# EasyEDAPro_River_Gauge_Rev_2_2026-01-11.net
KiCad netlist of a schematic drawn in EasyEDA Pro
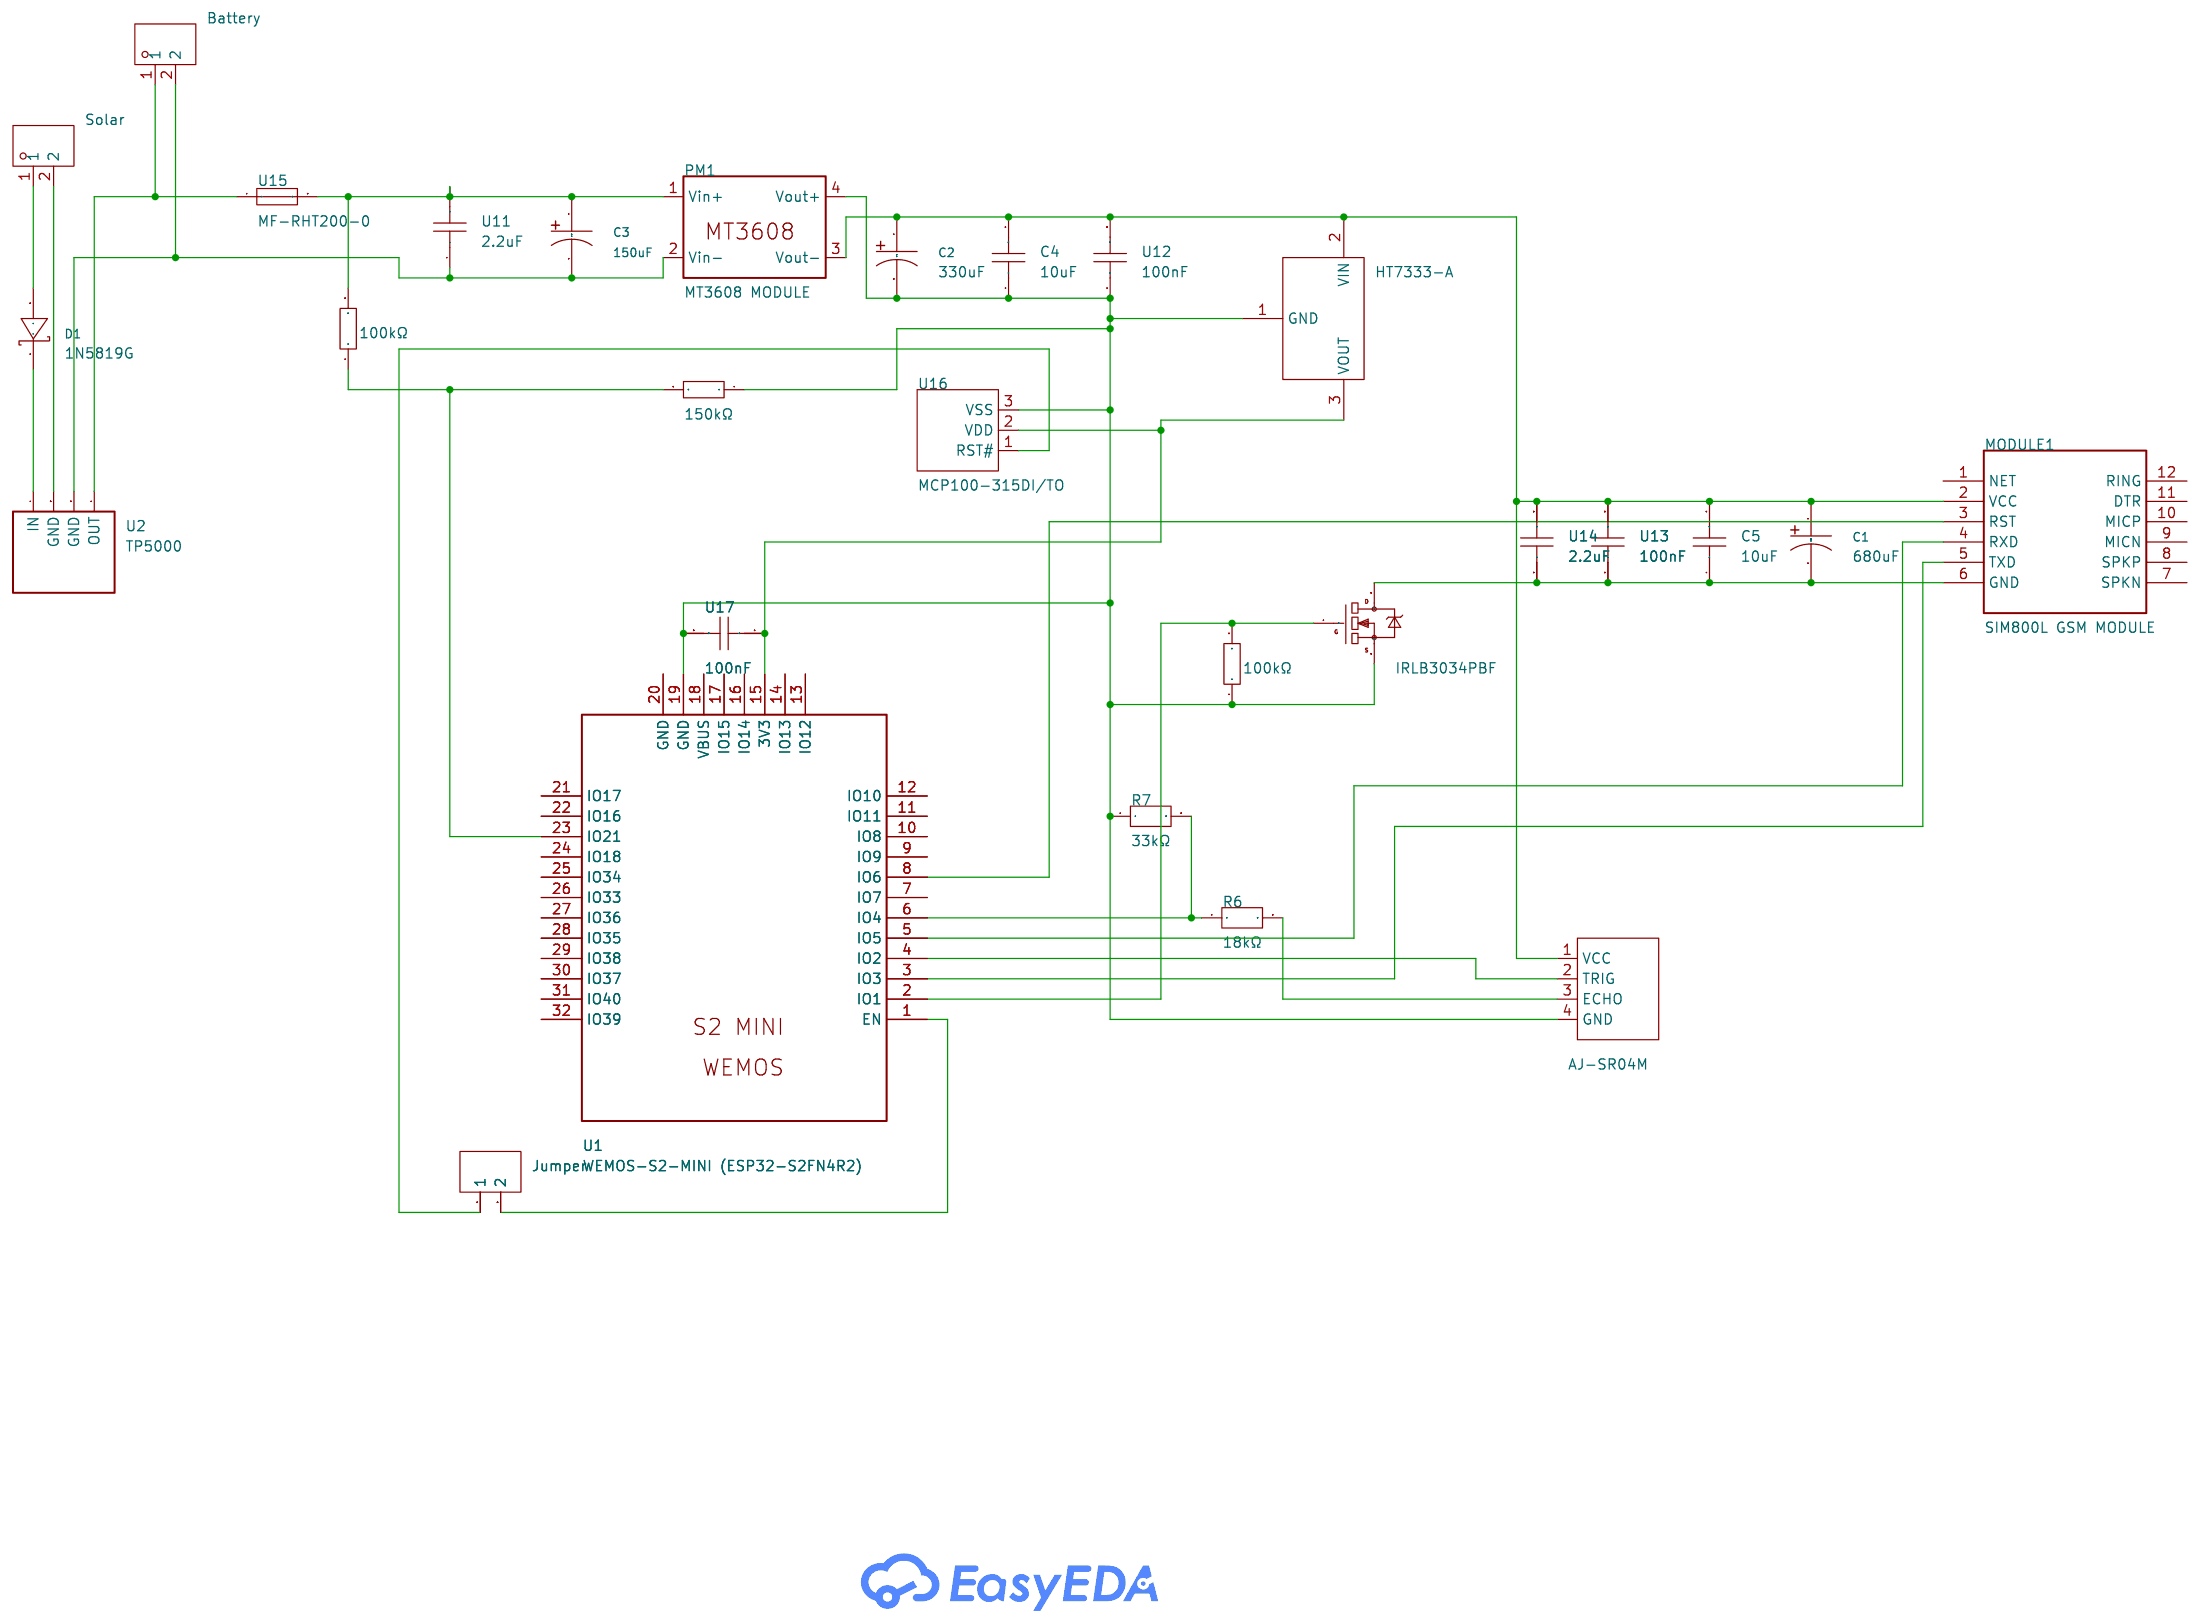
[diagram p0: schematic sheet]

(export (version "E")
  (design (tool "Eeschema 10.0.6"))
  (components
    (comp (ref "C1")
      (value "680uF")
      (footprint "easyedapro:CAP-TH_BD8.0-P3.50-D0.6-FD_1")
      (fields (field (name "Manufacturer Part") "EEUFR1A681") (field (name "Manufacturer") "PANASONIC(松下)"))
      (libsource (lib "easyedapro") (part "EEUFR1A681"))
    )
    (comp (ref "C2")
      (value "330uF")
      (footprint "easyedapro:CAP-TH_BD6.3-P2.50-D1.0-FD")
      (fields (field (name "Manufacturer Part") "EEUFS1A331") (field (name "Manufacturer") "PANASONIC(松下)"))
      (libsource (lib "easyedapro") (part "EEUFS1A331"))
    )
    (comp (ref "C3")
      (value "150uF")
      (footprint "easyedapro:CAP-TH_BD6.3-P2.50-D1.0-FD")
      (fields (field (name "Manufacturer Part") "EEUFS1A331") (field (name "Manufacturer") "PANASONIC(松下)"))
      (libsource (lib "easyedapro") (part "EEUFS1A331"))
    )
    (comp (ref "C4")
      (value "10uF")
      (footprint "easyedapro:CAP-TH_L4.5-W3.0-P2.50-D0.5")
      (fields (field (name "Manufacturer Part") "FG14X7R1A106KRT06") (field (name "Manufacturer") "TDK"))
      (libsource (lib "easyedapro") (part "FG14X7R1A106KRT06"))
    )
    (comp (ref "C5")
      (value "10uF")
      (footprint "easyedapro:CAP-TH_L4.5-W3.0-P2.50-D0.5")
      (fields (field (name "Manufacturer Part") "FG14X7R1A106KRT06") (field (name "Manufacturer") "TDK"))
      (libsource (lib "easyedapro") (part "FG14X7R1A106KRT06"))
    )
    (comp (ref "D1")
      (value "1N5819G")
      (footprint "easyedapro:DO-41_BD2.4-L4.7-P8.70-D0.9-RD")
      (fields (field (name "Manufacturer") "onsemi(安森美)"))
      (libsource (lib "easyedapro") (part "1N5819G"))
    )
    (comp (ref "H1")
      (value "Jumper")
      (footprint "easyedapro:HDR-TH_2P-P2.54-V-F")
      (libsource (lib "easyedapro") (part "Header-Female-2.54_1x2"))
    )
    (comp (ref "MODULE1")
      (value "SIM800L GSM MODULE")
      (footprint "easyedapro:SIM800L GSM MODULE")
      (libsource (lib "easyedapro") (part "SIM800L GSM MODULE"))
    )
    (comp (ref "PM1")
      (value "MT3608 MODULE")
      (footprint "easyedapro:MT3608")
      (libsource (lib "easyedapro") (part "MT3608 MODULE"))
    )
    (comp (ref "Q2")
      (value "IRLB3034PBF")
      (footprint "easyedapro:TO-220-3_L10.0-W4.5-P2.54-L")
      (fields (field (name "Manufacturer") "Infineon(英飞凌)"))
      (libsource (lib "easyedapro") (part "IRLB3034PBF"))
    )
    (comp (ref "R2")
      (value "100kΩ")
      (footprint "easyedapro:RES-TH_BD4.5-L11.0-P15.00-D0.7")
      (fields (field (name "Manufacturer Part") "MO2WS-100K±5%-TT63") (field (name "Manufacturer") "VO(翔胜)"))
      (libsource (lib "easyedapro") (part "MO2WS-100K±5%-TT63"))
    )
    (comp (ref "R3")
      (value "100kΩ")
      (footprint "easyedapro:RES-TH_BD4.5-L11.0-P15.00-D0.7")
      (fields (field (name "Manufacturer Part") "MO2WS-100K±5%-TT63") (field (name "Manufacturer") "VO(翔胜)"))
      (libsource (lib "easyedapro") (part "MO2WS-100K±5%-TT63"))
    )
    (comp (ref "R4")
      (value "150kΩ")
      (footprint "easyedapro:RES-TH_BD4.5-L11.0-P15.00-D0.7")
      (fields (field (name "Manufacturer Part") "MO2WS-100K±5%-TT63") (field (name "Manufacturer") "VO(翔胜)"))
      (libsource (lib "easyedapro") (part "MO2WS-100K±5%-TT63"))
    )
    (comp (ref "R6")
      (value "18kΩ")
      (footprint "easyedapro:RES-TH_BD2.4-L6.5-P10.50-D0.5")
      (fields
        (field (name "Manufacturer Part") "RNF14FTC18K0")
        (field (name "Manufacturer") "SEI(Stackpole Electronics Inc.)")
      )
      (libsource (lib "easyedapro") (part "RNF14FTC18K0"))
    )
    (comp (ref "R7")
      (value "33kΩ")
      (footprint "easyedapro:RES-TH_BD2.4-L6.5-P10.50-D0.5")
      (fields
        (field (name "Manufacturer Part") "RNF14FTC18K0")
        (field (name "Manufacturer") "SEI(Stackpole Electronics Inc.)")
      )
      (libsource (lib "easyedapro") (part "RNF14FTC18K0"))
    )
    (comp (ref "U1")
      (value "WEMOS-S2-MINI (ESP32-S2FN4R2)")
      (footprint "easyedapro:WEMOS-S2-MINI")
      (fields (field (name "Manufacturer Part") "Wemos") (field (name "Manufacturer") "WEMOS"))
      (libsource (lib "easyedapro") (part "WEMOS-S2-MINI (ESP32-S2FN4R2)"))
    )
    (comp (ref "U2")
      (value "TP5000")
      (footprint "easyedapro:TP5000")
      (libsource (lib "easyedapro") (part "TP5000"))
    )
    (comp (ref "U7")
      (value "Solar")
      (footprint "easyedapro:CONN-TH_2P-P3.50_KEFA_KF2EDGJVC-3.5-2P")
      (fields (field (name "Manufacturer Part") "KF2EDGJVC-3.5-2P"))
      (libsource (lib "easyedapro") (part "KF2EDGJVC-3.5-2P"))
    )
    (comp (ref "U8")
      (value "Battery")
      (footprint "easyedapro:CONN-TH_2P-P3.50_KEFA_KF2EDGJVC-3.5-2P")
      (fields (field (name "Manufacturer Part") "KF2EDGJVC-3.5-2P"))
      (libsource (lib "easyedapro") (part "KF2EDGJVC-3.5-2P"))
    )
    (comp (ref "U9")
      (value "AJ-SR04M")
      (footprint "easyedapro:TH_HC-SR04V")
      (fields
        (field (name "Manufacturer Part") "HC-SR04")
        (field (name "Manufacturer") "Universal Microelectronics")
      )
      (libsource (lib "easyedapro") (part "HC-SR04"))
    )
    (comp (ref "U10")
      (value "HT7333-A")
      (footprint "easyedapro:TO-92-3_L5.1-W4.1-P1.27-L")
      (fields (field (name "Manufacturer") "HOLTEK(合泰/盛群)"))
      (libsource (lib "easyedapro") (part "HT7333-A_C73726"))
    )
    (comp (ref "U11")
      (value "2.2uF")
      (footprint "easyedapro:CAP-TH_L4.0-W2.5-P2.50-D0.5")
      (fields (field (name "Manufacturer Part") "FG18X7R1A225KRT06") (field (name "Manufacturer") "TDK"))
      (libsource (lib "easyedapro") (part "FG18X7R1A225KRT06"))
    )
    (comp (ref "U12")
      (value "100nF")
      (footprint "easyedapro:CAP-TH_L3.6-W2.3-P2.5-D0.6")
      (description "Capacitance:100nF Tolerance:±10% Tolerance:±10% Voltage Rating:50V Temperature Coefficient:X7R")
      (fields (field (name "Manufacturer Part") "K104K15X7RF53L2") (field (name "Manufacturer") "VISHAY(威世)"))
      (libsource (lib "easyedapro") (part "K104K15X7RF53L2"))
    )
    (comp (ref "U13")
      (value "100nF")
      (footprint "easyedapro:CAP-TH_L3.6-W2.3-P2.5-D0.6")
      (description "Capacitance:100nF Tolerance:±10% Tolerance:±10% Voltage Rating:50V Temperature Coefficient:X7R")
      (fields (field (name "Manufacturer Part") "K104K15X7RF53L2") (field (name "Manufacturer") "VISHAY(威世)"))
      (libsource (lib "easyedapro") (part "K104K15X7RF53L2"))
    )
    (comp (ref "U14")
      (value "2.2uF")
      (footprint "easyedapro:CAP-TH_L4.0-W2.5-P2.50-D0.5")
      (fields (field (name "Manufacturer Part") "FG18X7R1A225KRT06") (field (name "Manufacturer") "TDK"))
      (libsource (lib "easyedapro") (part "FG18X7R1A225KRT06"))
    )
    (comp (ref "U15")
      (value "MF-RHT200-0")
      (footprint "easyedapro:FUSE-TH_L9.4-W3.0-P5.10-D1.0-S2.10")
      (fields (field (name "Manufacturer") "BOURNS"))
      (libsource (lib "easyedapro") (part "MF-RHT200-0"))
    )
    (comp (ref "U16")
      (value "MCP100-315DI/TO")
      (footprint "easyedapro:TO-92-3_L4.8-W3.7-P1.27-L")
      (fields (field (name "Manufacturer") "MICROCHIP(美国微芯)"))
      (libsource (lib "easyedapro") (part "MCP100-315DI/TO"))
    )
    (comp (ref "U17")
      (value "100nF")
      (footprint "easyedapro:CAP-TH_L3.6-W2.3-P2.5-D0.6")
      (description "Capacitance:100nF Tolerance:±10% Tolerance:±10% Voltage Rating:50V Temperature Coefficient:X7R")
      (fields (field (name "Manufacturer Part") "K104K15X7RF53L2") (field (name "Manufacturer") "VISHAY(威世)"))
      (libsource (lib "easyedapro") (part "K104K15X7RF53L2"))
    )
  )
  (nets
    (net (code "1") (name "Net-(D1-A)") (class "Default")
      (node (ref "D1") (pin "2") (pinfunction "A_2") (pintype "input"))
      (node (ref "U7") (pin "1") (pinfunction "1_1") (pintype "unspecified"))
    )
    (net (code "2") (name "Net-(D1-K)") (class "Default")
      (node (ref "D1") (pin "1") (pinfunction "K_1") (pintype "input"))
      (node (ref "U2") (pin "4") (pinfunction "IN_4") (pintype "unspecified"))
    )
    (net (code "3") (name "Net-(MODULE1-GND)") (class "Default")
      (node (ref "C1") (pin "2") (pinfunction "2_2") (pintype "input"))
      (node (ref "C5") (pin "1") (pinfunction "1_1") (pintype "unspecified"))
      (node (ref "MODULE1") (pin "6") (pinfunction "GND_6") (pintype "unspecified"))
      (node (ref "Q2") (pin "2") (pinfunction "D_2") (pintype "unspecified"))
      (node (ref "U13") (pin "1") (pinfunction "1_1") (pintype "unspecified"))
      (node (ref "U14") (pin "1") (pinfunction "1_1") (pintype "unspecified"))
    )
    (net (code "4") (name "Net-(MODULE1-RST)") (class "Default")
      (node (ref "MODULE1") (pin "3") (pinfunction "RST_3") (pintype "unspecified"))
      (node (ref "U1") (pin "8") (pinfunction "IO6_8") (pintype "bidirectional"))
    )
    (net (code "5") (name "Net-(MODULE1-RXD)") (class "Default")
      (node (ref "MODULE1") (pin "4") (pinfunction "RXD_4") (pintype "unspecified"))
      (node (ref "U1") (pin "5") (pinfunction "IO5_5") (pintype "bidirectional"))
    )
    (net (code "6") (name "Net-(MODULE1-TXD)") (class "Default")
      (node (ref "MODULE1") (pin "5") (pinfunction "TXD_5") (pintype "unspecified"))
      (node (ref "U1") (pin "3") (pinfunction "IO3_3") (pintype "bidirectional"))
    )
    (net (code "7") (name "Net-(MODULE1-VCC)") (class "Default")
      (node (ref "C1") (pin "1") (pinfunction "1_1") (pintype "input"))
      (node (ref "C2") (pin "1") (pinfunction "1_1") (pintype "input"))
      (node (ref "C4") (pin "2") (pinfunction "2_2") (pintype "unspecified"))
      (node (ref "C5") (pin "2") (pinfunction "2_2") (pintype "unspecified"))
      (node (ref "MODULE1") (pin "2") (pinfunction "VCC_2") (pintype "unspecified"))
      (node (ref "PM1") (pin "3") (pinfunction "Vout-_3") (pintype "unspecified"))
      (node (ref "U10") (pin "2") (pinfunction "VIN_2") (pintype "unspecified"))
      (node (ref "U12") (pin "2") (pinfunction "2_2") (pintype "unspecified"))
      (node (ref "U13") (pin "2") (pinfunction "2_2") (pintype "unspecified"))
      (node (ref "U14") (pin "2") (pinfunction "2_2") (pintype "unspecified"))
      (node (ref "U9") (pin "1") (pinfunction "VCC_1") (pintype "unspecified"))
    )
    (net (code "8") (name "Net-(PM1-Vin+)") (class "Default")
      (node (ref "C3") (pin "1") (pinfunction "1_1") (pintype "input"))
      (node (ref "PM1") (pin "1") (pinfunction "Vin+_1") (pintype "unspecified"))
      (node (ref "R3") (pin "2") (pinfunction "2_2") (pintype "unspecified"))
      (node (ref "U11") (pin "2") (pinfunction "2_2") (pintype "unspecified"))
      (node (ref "U15") (pin "2") (pinfunction "2_2") (pintype "unspecified"))
    )
    (net (code "9") (name "Net-(PM1-Vin-)") (class "Default")
      (node (ref "C3") (pin "2") (pinfunction "2_2") (pintype "input"))
      (node (ref "PM1") (pin "2") (pinfunction "Vin-_2") (pintype "unspecified"))
      (node (ref "U11") (pin "1") (pinfunction "1_1") (pintype "unspecified"))
      (node (ref "U2") (pin "2") (pinfunction "GND_2") (pintype "unspecified"))
      (node (ref "U8") (pin "2") (pinfunction "2_2") (pintype "unspecified"))
    )
    (net (code "10") (name "Net-(PM1-Vout+)") (class "Default")
      (node (ref "C2") (pin "2") (pinfunction "2_2") (pintype "input"))
      (node (ref "C4") (pin "1") (pinfunction "1_1") (pintype "unspecified"))
      (node (ref "PM1") (pin "4") (pinfunction "Vout+_4") (pintype "unspecified"))
      (node (ref "Q2") (pin "3") (pinfunction "S_3") (pintype "unspecified"))
      (node (ref "R2") (pin "1") (pinfunction "1_1") (pintype "unspecified"))
      (node (ref "R4") (pin "1") (pinfunction "1_1") (pintype "unspecified"))
      (node (ref "R7") (pin "1") (pinfunction "1_1") (pintype "unspecified"))
      (node (ref "U1") (pin "19") (pinfunction "GND_19") (pintype "unspecified"))
      (node (ref "U10") (pin "1") (pinfunction "GND_1") (pintype "unspecified"))
      (node (ref "U12") (pin "1") (pinfunction "1_1") (pintype "unspecified"))
      (node (ref "U16") (pin "3") (pinfunction "VSS_3") (pintype "unspecified"))
      (node (ref "U17") (pin "2") (pinfunction "2_2") (pintype "unspecified"))
      (node (ref "U9") (pin "4") (pinfunction "GND_4") (pintype "unspecified"))
    )
    (net (code "11") (name "Net-(Q2-G)") (class "Default")
      (node (ref "Q2") (pin "1") (pinfunction "G_1") (pintype "unspecified"))
      (node (ref "R2") (pin "2") (pinfunction "2_2") (pintype "unspecified"))
      (node (ref "U1") (pin "2") (pinfunction "IO1_2") (pintype "bidirectional"))
    )
    (net (code "12") (name "Net-(U1-3V3)") (class "Default")
      (node (ref "U1") (pin "15") (pinfunction "3V3_15") (pintype "unspecified"))
      (node (ref "U10") (pin "3") (pinfunction "VOUT_3") (pintype "unspecified"))
      (node (ref "U16") (pin "2") (pinfunction "VDD_2") (pintype "unspecified"))
      (node (ref "U17") (pin "1") (pinfunction "1_1") (pintype "unspecified"))
    )
    (net (code "13") (name "Net-(U1-EN)") (class "Default")
      (node (ref "H1") (pin "2") (pinfunction "2_2") (pintype "input"))
      (node (ref "U1") (pin "1") (pinfunction "EN_1") (pintype "input"))
    )
    (net (code "14") (name "Net-(U1-IO2)") (class "Default")
      (node (ref "U1") (pin "4") (pinfunction "IO2_4") (pintype "bidirectional"))
      (node (ref "U9") (pin "2") (pinfunction "TRIG_2") (pintype "unspecified"))
    )
    (net (code "15") (name "Net-(U1-IO4)") (class "Default")
      (node (ref "R6") (pin "1") (pinfunction "1_1") (pintype "unspecified"))
      (node (ref "R7") (pin "2") (pinfunction "2_2") (pintype "unspecified"))
      (node (ref "U1") (pin "6") (pinfunction "IO4_6") (pintype "bidirectional"))
    )
    (net (code "16") (name "Net-(U1-IO21)") (class "Default")
      (node (ref "R3") (pin "1") (pinfunction "1_1") (pintype "unspecified"))
      (node (ref "R4") (pin "2") (pinfunction "2_2") (pintype "unspecified"))
      (node (ref "U1") (pin "23") (pinfunction "IO21_23") (pintype "unspecified"))
    )
    (net (code "17") (name "Net-(U2-GND-Pad3)") (class "Default")
      (node (ref "U2") (pin "3") (pinfunction "GND_3") (pintype "unspecified"))
      (node (ref "U7") (pin "2") (pinfunction "2_2") (pintype "unspecified"))
    )
    (net (code "18") (name "Net-(U2-OUT)") (class "Default")
      (node (ref "U15") (pin "1") (pinfunction "1_1") (pintype "unspecified"))
      (node (ref "U2") (pin "1") (pinfunction "OUT_1") (pintype "unspecified"))
      (node (ref "U8") (pin "1") (pinfunction "1_1") (pintype "unspecified"))
    )
    (net (code "19") (name "Net-(U9-ECHO)") (class "Default")
      (node (ref "R6") (pin "2") (pinfunction "2_2") (pintype "unspecified"))
      (node (ref "U9") (pin "3") (pinfunction "ECHO_3") (pintype "unspecified"))
    )
    (net (code "20") (name "Net-(U16-RST#)") (class "Default")
      (node (ref "H1") (pin "1") (pinfunction "1_1") (pintype "input"))
      (node (ref "U16") (pin "1") (pinfunction "RST#_1") (pintype "unspecified"))
    )
    (net (code "21") (name "unconnected-(MODULE1-DTR-Pad11)") (class "Default")
      (node (ref "MODULE1") (pin "11") (pinfunction "DTR_11") (pintype "unspecified"))
    )
    (net (code "22") (name "unconnected-(MODULE1-MICN-Pad9)") (class "Default")
      (node (ref "MODULE1") (pin "9") (pinfunction "MICN_9") (pintype "unspecified"))
    )
    (net (code "23") (name "unconnected-(MODULE1-MICP-Pad10)") (class "Default")
      (node (ref "MODULE1") (pin "10") (pinfunction "MICP_10") (pintype "unspecified"))
    )
    (net (code "24") (name "unconnected-(MODULE1-NET-Pad1)") (class "Default")
      (node (ref "MODULE1") (pin "1") (pinfunction "NET_1") (pintype "unspecified"))
    )
    (net (code "25") (name "unconnected-(MODULE1-RING-Pad12)") (class "Default")
      (node (ref "MODULE1") (pin "12") (pinfunction "RING_12") (pintype "unspecified"))
    )
    (net (code "26") (name "unconnected-(MODULE1-SPKN-Pad7)") (class "Default")
      (node (ref "MODULE1") (pin "7") (pinfunction "SPKN_7") (pintype "unspecified"))
    )
    (net (code "27") (name "unconnected-(MODULE1-SPKP-Pad8)") (class "Default")
      (node (ref "MODULE1") (pin "8") (pinfunction "SPKP_8") (pintype "unspecified"))
    )
    (net (code "28") (name "unconnected-(U1-GND-Pad20)") (class "Default")
      (node (ref "U1") (pin "20") (pinfunction "GND_20") (pintype "unspecified"))
    )
    (net (code "29") (name "unconnected-(U1-IO7-Pad7)") (class "Default")
      (node (ref "U1") (pin "7") (pinfunction "IO7_7") (pintype "bidirectional"))
    )
    (net (code "30") (name "unconnected-(U1-IO8-Pad10)") (class "Default")
      (node (ref "U1") (pin "10") (pinfunction "IO8_10") (pintype "bidirectional"))
    )
    (net (code "31") (name "unconnected-(U1-IO9-Pad9)") (class "Default")
      (node (ref "U1") (pin "9") (pinfunction "IO9_9") (pintype "bidirectional"))
    )
    (net (code "32") (name "unconnected-(U1-IO10-Pad12)") (class "Default")
      (node (ref "U1") (pin "12") (pinfunction "IO10_12") (pintype "bidirectional"))
    )
    (net (code "33") (name "unconnected-(U1-IO11-Pad11)") (class "Default")
      (node (ref "U1") (pin "11") (pinfunction "IO11_11") (pintype "bidirectional"))
    )
    (net (code "34") (name "unconnected-(U1-IO12-Pad13)") (class "Default")
      (node (ref "U1") (pin "13") (pinfunction "IO12_13") (pintype "bidirectional"))
    )
    (net (code "35") (name "unconnected-(U1-IO13-Pad14)") (class "Default")
      (node (ref "U1") (pin "14") (pinfunction "IO13_14") (pintype "bidirectional"))
    )
    (net (code "36") (name "unconnected-(U1-IO14-Pad16)") (class "Default")
      (node (ref "U1") (pin "16") (pinfunction "IO14_16") (pintype "bidirectional"))
    )
    (net (code "37") (name "unconnected-(U1-IO15-Pad17)") (class "Default")
      (node (ref "U1") (pin "17") (pinfunction "IO15_17") (pintype "bidirectional"))
    )
    (net (code "38") (name "unconnected-(U1-IO16-Pad22)") (class "Default")
      (node (ref "U1") (pin "22") (pinfunction "IO16_22") (pintype "unspecified"))
    )
    (net (code "39") (name "unconnected-(U1-IO17-Pad21)") (class "Default")
      (node (ref "U1") (pin "21") (pinfunction "IO17_21") (pintype "unspecified"))
    )
    (net (code "40") (name "unconnected-(U1-IO18-Pad24)") (class "Default")
      (node (ref "U1") (pin "24") (pinfunction "IO18_24") (pintype "unspecified"))
    )
    (net (code "41") (name "unconnected-(U1-IO33-Pad26)") (class "Default")
      (node (ref "U1") (pin "26") (pinfunction "IO33_26") (pintype "unspecified"))
    )
    (net (code "42") (name "unconnected-(U1-IO34-Pad25)") (class "Default")
      (node (ref "U1") (pin "25") (pinfunction "IO34_25") (pintype "unspecified"))
    )
    (net (code "43") (name "unconnected-(U1-IO35-Pad28)") (class "Default")
      (node (ref "U1") (pin "28") (pinfunction "IO35_28") (pintype "unspecified"))
    )
    (net (code "44") (name "unconnected-(U1-IO36-Pad27)") (class "Default")
      (node (ref "U1") (pin "27") (pinfunction "IO36_27") (pintype "unspecified"))
    )
    (net (code "45") (name "unconnected-(U1-IO37-Pad30)") (class "Default")
      (node (ref "U1") (pin "30") (pinfunction "IO37_30") (pintype "unspecified"))
    )
    (net (code "46") (name "unconnected-(U1-IO38-Pad29)") (class "Default")
      (node (ref "U1") (pin "29") (pinfunction "IO38_29") (pintype "unspecified"))
    )
    (net (code "47") (name "unconnected-(U1-IO39-Pad32)") (class "Default")
      (node (ref "U1") (pin "32") (pinfunction "IO39_32") (pintype "unspecified"))
    )
    (net (code "48") (name "unconnected-(U1-IO40-Pad31)") (class "Default")
      (node (ref "U1") (pin "31") (pinfunction "IO40_31") (pintype "unspecified"))
    )
    (net (code "49") (name "unconnected-(U1-VBUS-Pad18)") (class "Default")
      (node (ref "U1") (pin "18") (pinfunction "VBUS_18") (pintype "bidirectional"))
    )
  )
)
